# main.net
KiCad netlist of a schematic drawn in EAGLE
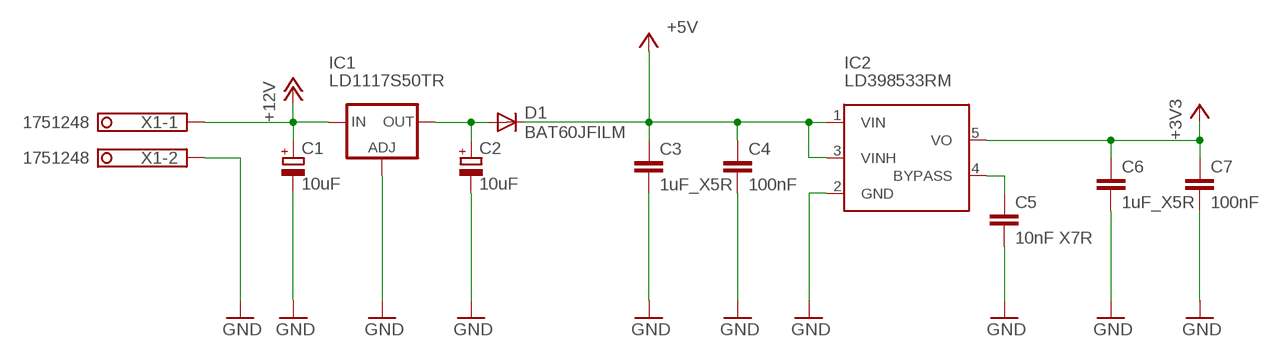
[diagram p0: schematic, sheet 1]
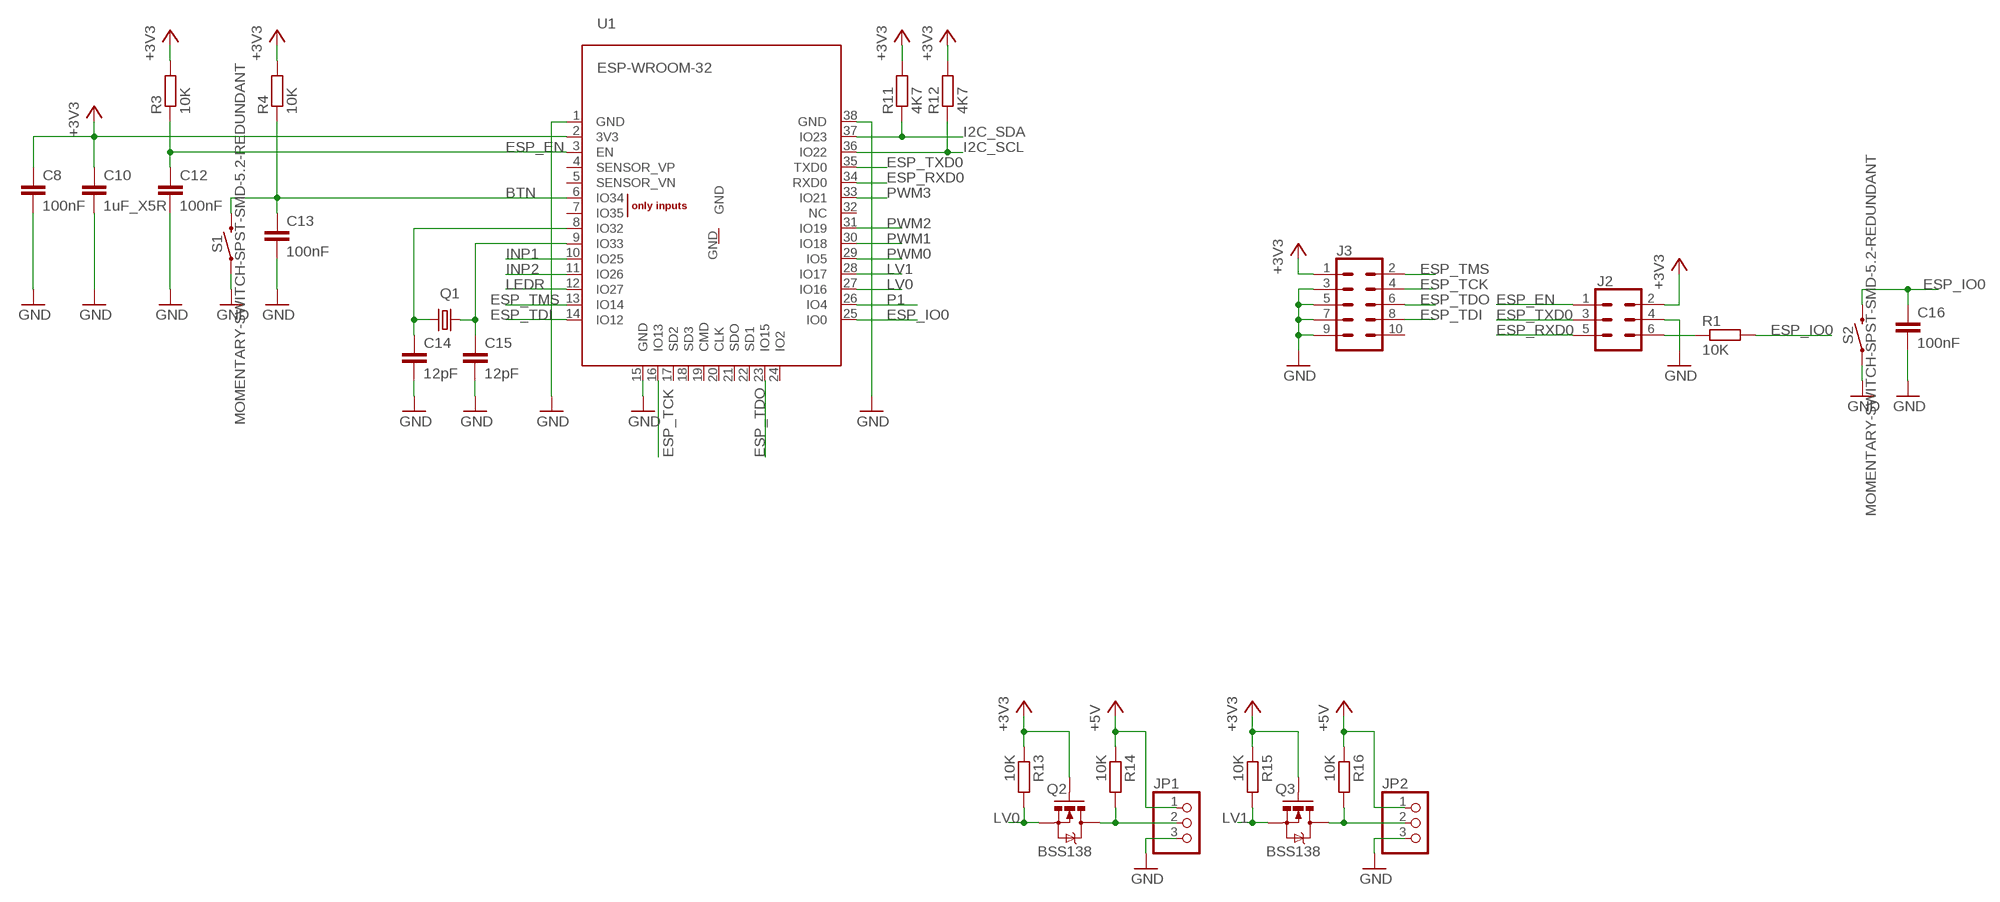
[diagram p1: schematic, sheet 2]
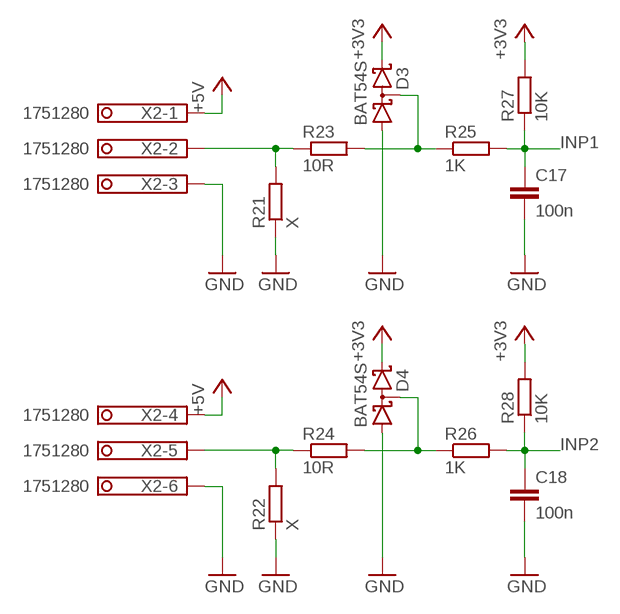
[diagram p2: schematic, sheet 3]
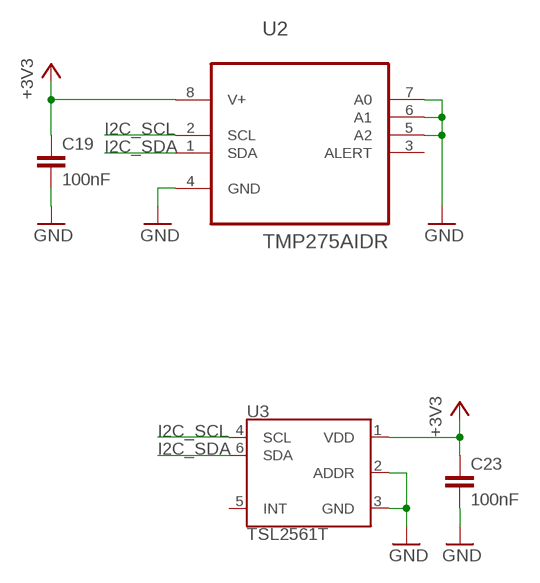
[diagram p3: schematic, sheet 4]
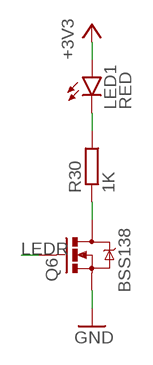
[diagram p4: schematic, sheet 5]
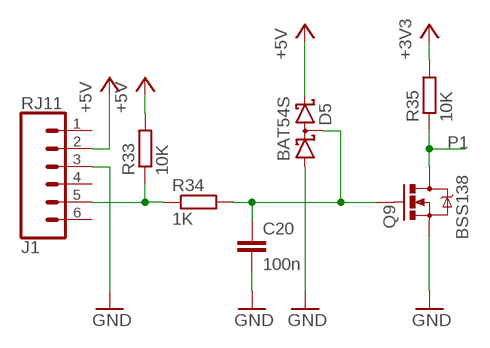
[diagram p5: schematic, sheet 6]
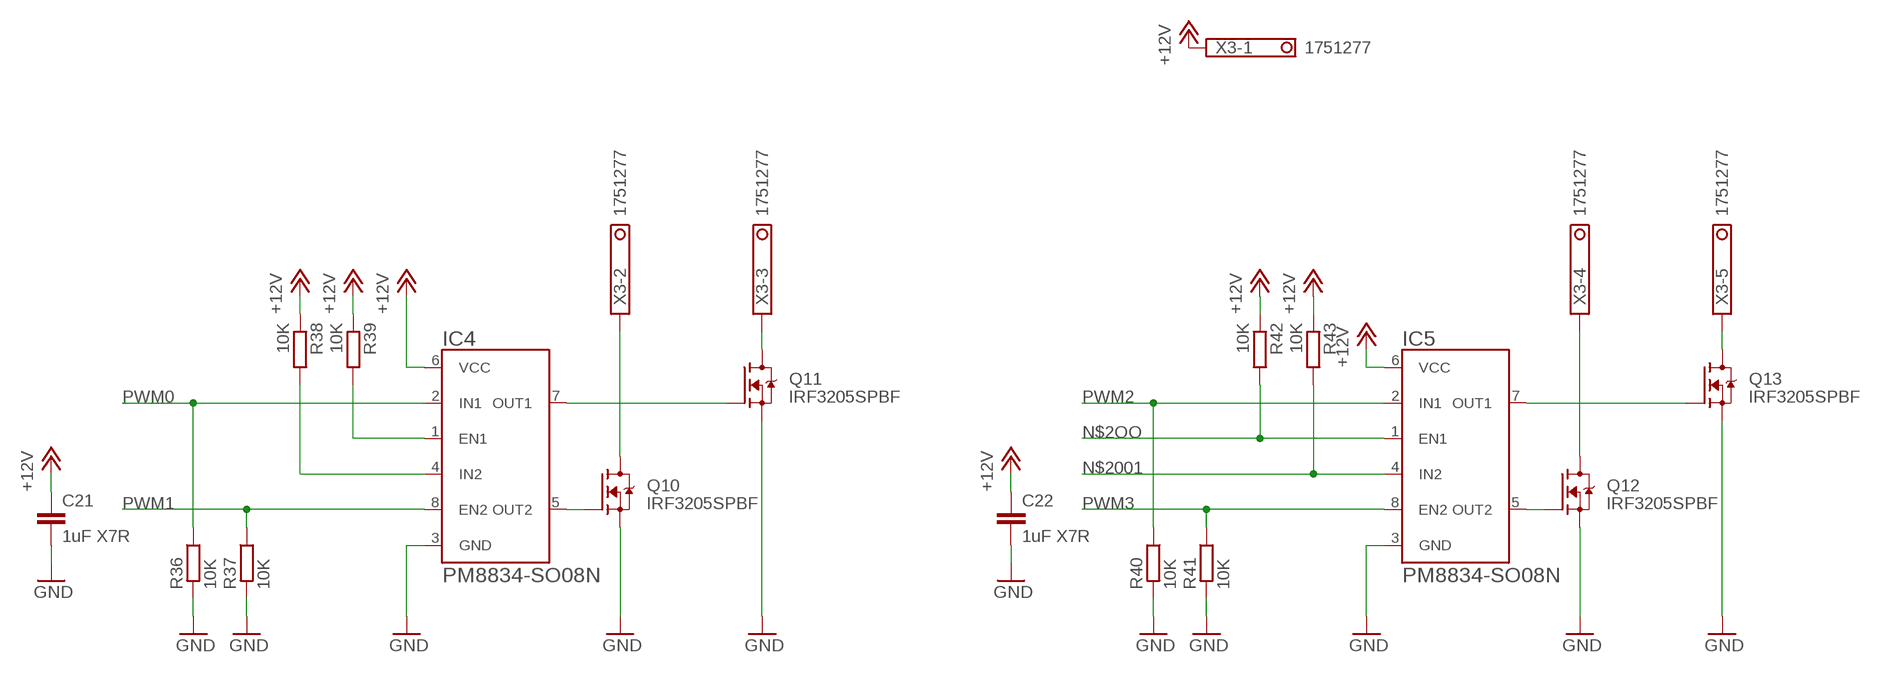
[diagram p6: schematic, sheet 7]
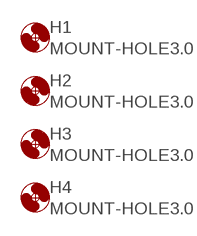
[diagram p7: schematic, sheet 8]

(export (version "E")
  (design (tool "Eeschema 10.0.6"))
  (components
    (comp (ref "C21")
      (value "1uF X7R")
      (footprint "eagle-import:C0805")
      (libsource (lib "eagle-import") (part "resistor_348_C-EUC0805"))
    )
    (comp (ref "C22")
      (value "1uF X7R")
      (footprint "eagle-import:C0805")
      (libsource (lib "eagle-import") (part "resistor_348_C-EUC0805"))
    )
    (comp (ref "IC4")
      (value "PM8834-SO08N")
      (footprint "eagle-import:SO08N")
      (fields (field (name "MF") "STMicroelectronics") (field (name "MP") "PM8834"))
      (libsource (lib "eagle-import") (part "PM8834-SO08N"))
    )
    (comp (ref "IC5")
      (value "PM8834-SO08N")
      (footprint "eagle-import:SO08N")
      (fields (field (name "MF") "STMicroelectronics") (field (name "MP") "PM8834"))
      (libsource (lib "eagle-import") (part "PM8834-SO08N"))
    )
    (comp (ref "Q10")
      (value "IRF3205SPBF")
      (footprint "eagle-import:TRANS_IRF3205SPBF")
      (fields (field (name "MF") "Infineon Technologies"))
      (libsource (lib "eagle-import") (part "IRF3205SPBF"))
    )
    (comp (ref "Q11")
      (value "IRF3205SPBF")
      (footprint "eagle-import:TRANS_IRF3205SPBF")
      (fields (field (name "MF") "Infineon Technologies"))
      (libsource (lib "eagle-import") (part "IRF3205SPBF"))
    )
    (comp (ref "Q12")
      (value "IRF3205SPBF")
      (footprint "eagle-import:TRANS_IRF3205SPBF")
      (fields (field (name "MF") "Infineon Technologies"))
      (libsource (lib "eagle-import") (part "IRF3205SPBF"))
    )
    (comp (ref "Q13")
      (value "IRF3205SPBF")
      (footprint "eagle-import:TRANS_IRF3205SPBF")
      (fields (field (name "MF") "Infineon Technologies"))
      (libsource (lib "eagle-import") (part "IRF3205SPBF"))
    )
    (comp (ref "R36")
      (value "10K")
      (footprint "eagle-import:R0805")
      (libsource (lib "eagle-import") (part "resistor_348_R-EU_R0805"))
    )
    (comp (ref "R37")
      (value "10K")
      (footprint "eagle-import:R0805")
      (libsource (lib "eagle-import") (part "resistor_348_R-EU_R0805"))
    )
    (comp (ref "R38")
      (value "10K")
      (footprint "eagle-import:R0805")
      (libsource (lib "eagle-import") (part "resistor_348_R-EU_R0805"))
    )
    (comp (ref "R39")
      (value "10K")
      (footprint "eagle-import:R0805")
      (libsource (lib "eagle-import") (part "resistor_348_R-EU_R0805"))
    )
    (comp (ref "R40")
      (value "10K")
      (footprint "eagle-import:R0805")
      (libsource (lib "eagle-import") (part "resistor_348_R-EU_R0805"))
    )
    (comp (ref "R41")
      (value "10K")
      (footprint "eagle-import:R0805")
      (libsource (lib "eagle-import") (part "resistor_348_R-EU_R0805"))
    )
    (comp (ref "R42")
      (value "10K")
      (footprint "eagle-import:R0805")
      (libsource (lib "eagle-import") (part "resistor_348_R-EU_R0805"))
    )
    (comp (ref "R43")
      (value "10K")
      (footprint "eagle-import:R0805")
      (libsource (lib "eagle-import") (part "resistor_348_R-EU_R0805"))
    )
    (comp (ref "X3")
      (value "1751277")
      (footprint "eagle-import:1751277")
      (libsource (lib "eagle-import") (part "1751277"))
    )
    (comp (ref "C19")
      (value "100nF")
      (footprint "eagle-import:C0805")
      (libsource (lib "eagle-import") (part "C-EUC0805"))
    )
    (comp (ref "C23")
      (value "100nF")
      (footprint "eagle-import:C0805")
      (libsource (lib "eagle-import") (part "C-EUC0805"))
    )
    (comp (ref "U2")
      (value "TMP275AIDR")
      (footprint "eagle-import:SOIC127P600X175-8N")
      (fields (field (name "MF") "Texas Instruments"))
      (libsource (lib "eagle-import") (part "TMP275AIDR"))
    )
    (comp (ref "U3")
      (value "TSL2561T")
      (footprint "eagle-import:TMB-6")
      (libsource (lib "eagle-import") (part "TSL2561T"))
    )
    (comp (ref "C20")
      (value "100n")
      (footprint "eagle-import:C0805")
      (libsource (lib "eagle-import") (part "resistor_348_C-EUC0805"))
    )
    (comp (ref "D5")
      (value "BAT54S")
      (footprint "eagle-import:SOT23")
      (libsource (lib "eagle-import") (part "BAT54S"))
    )
    (comp (ref "J1")
      (value "RJ11")
      (footprint "eagle-import:RJ11-6")
      (libsource (lib "eagle-import") (part "RJ11-6"))
    )
    (comp (ref "Q9")
      (value "BSS138")
      (footprint "eagle-import:SOT23-3")
      (libsource (lib "eagle-import") (part "MOSFET-NCHANNELSMD"))
    )
    (comp (ref "R33")
      (value "10K")
      (footprint "eagle-import:R0805")
      (libsource (lib "eagle-import") (part "resistor_348_R-EU_R0805"))
    )
    (comp (ref "R34")
      (value "1K")
      (footprint "eagle-import:R0805")
      (libsource (lib "eagle-import") (part "resistor_348_R-EU_R0805"))
    )
    (comp (ref "R35")
      (value "10K")
      (footprint "eagle-import:R0805")
      (libsource (lib "eagle-import") (part "resistor_348_R-EU_R0805"))
    )
    (comp (ref "C8")
      (value "100nF")
      (footprint "eagle-import:C0805")
      (libsource (lib "eagle-import") (part "resistor_348_C-EUC0805"))
    )
    (comp (ref "C10")
      (value "1uF_X5R")
      (footprint "eagle-import:C0805")
      (libsource (lib "eagle-import") (part "resistor_348_C-EUC0805"))
    )
    (comp (ref "C12")
      (value "100nF")
      (footprint "eagle-import:C0805")
      (libsource (lib "eagle-import") (part "resistor_348_C-EUC0805"))
    )
    (comp (ref "C13")
      (value "100nF")
      (footprint "eagle-import:C0805")
      (libsource (lib "eagle-import") (part "resistor_348_C-EUC0805"))
    )
    (comp (ref "C14")
      (value "12pF")
      (footprint "eagle-import:C0805")
      (libsource (lib "eagle-import") (part "resistor_348_C-EUC0805"))
    )
    (comp (ref "C15")
      (value "12pF")
      (footprint "eagle-import:C0805")
      (libsource (lib "eagle-import") (part "resistor_348_C-EUC0805"))
    )
    (comp (ref "C16")
      (value "100nF")
      (footprint "eagle-import:C0805")
      (libsource (lib "eagle-import") (part "resistor_348_C-EUC0805"))
    )
    (comp (ref "J2")
      (value "CONN_03X2SHROUD")
      (footprint "eagle-import:2X3-SHROUDED")
      (libsource (lib "eagle-import") (part "CONN_03X2SHROUD"))
    )
    (comp (ref "J3")
      (value "CONN_05X2SHD")
      (footprint "eagle-import:2X5-SHROUDED")
      (libsource (lib "eagle-import") (part "CONN_05X2SHD"))
    )
    (comp (ref "JP1")
      (value "PINHD-1X3")
      (footprint "eagle-import:1X03")
      (libsource (lib "eagle-import") (part "PINHD-1X3"))
    )
    (comp (ref "JP2")
      (value "PINHD-1X3")
      (footprint "eagle-import:1X03")
      (libsource (lib "eagle-import") (part "PINHD-1X3"))
    )
    (comp (ref "Q1")
      (value "CRYSTALTC38H")
      (footprint "eagle-import:TC38H")
      (libsource (lib "eagle-import") (part "CRYSTALTC38H"))
    )
    (comp (ref "Q2")
      (value "BSS138")
      (footprint "eagle-import:SOT23-3")
      (libsource (lib "eagle-import") (part "MOSFET-NCHANNELSMD"))
    )
    (comp (ref "Q3")
      (value "BSS138")
      (footprint "eagle-import:SOT23-3")
      (libsource (lib "eagle-import") (part "MOSFET-NCHANNELSMD"))
    )
    (comp (ref "R1")
      (value "10K")
      (footprint "eagle-import:R0805")
      (libsource (lib "eagle-import") (part "resistor_348_R-EU_R0805"))
    )
    (comp (ref "R3")
      (value "10K")
      (footprint "eagle-import:R0805")
      (libsource (lib "eagle-import") (part "R-EU_R0805"))
    )
    (comp (ref "R4")
      (value "10K")
      (footprint "eagle-import:R0805")
      (libsource (lib "eagle-import") (part "R-EU_R0805"))
    )
    (comp (ref "R11")
      (value "4K7")
      (footprint "eagle-import:R0805")
      (libsource (lib "eagle-import") (part "resistor_348_R-EU_R0805"))
    )
    (comp (ref "R12")
      (value "4K7")
      (footprint "eagle-import:R0805")
      (libsource (lib "eagle-import") (part "resistor_348_R-EU_R0805"))
    )
    (comp (ref "R13")
      (value "10K")
      (footprint "eagle-import:R0805")
      (libsource (lib "eagle-import") (part "resistor_348_R-EU_R0805"))
    )
    (comp (ref "R14")
      (value "10K")
      (footprint "eagle-import:R0805")
      (libsource (lib "eagle-import") (part "resistor_348_R-EU_R0805"))
    )
    (comp (ref "R15")
      (value "10K")
      (footprint "eagle-import:R0805")
      (libsource (lib "eagle-import") (part "resistor_348_R-EU_R0805"))
    )
    (comp (ref "R16")
      (value "10K")
      (footprint "eagle-import:R0805")
      (libsource (lib "eagle-import") (part "resistor_348_R-EU_R0805"))
    )
    (comp (ref "S1")
      (value "MOMENTARY-SWITCH-SPST-SMD-5.2-REDUNDANT")
      (footprint "eagle-import:TACTILE_SWITCH_SMD_5.2MM")
      (libsource (lib "eagle-import") (part "MOMENTARY-SWITCH-SPST-SMD-5.2-REDUNDANT"))
    )
    (comp (ref "S2")
      (value "MOMENTARY-SWITCH-SPST-SMD-5.2-REDUNDANT")
      (footprint "eagle-import:TACTILE_SWITCH_SMD_5.2MM")
      (libsource (lib "eagle-import") (part "MOMENTARY-SWITCH-SPST-SMD-5.2-REDUNDANT"))
    )
    (comp (ref "U1")
      (value "ESP-WROOM-32")
      (footprint "eagle-import:ESP-WROOM-32")
      (libsource (lib "eagle-import") (part "ESP-WROOM-32"))
    )
    (comp (ref "H1")
      (value "MOUNT-HOLE3.0")
      (footprint "eagle-import:3,0")
      (libsource (lib "eagle-import") (part "MOUNT-HOLE3.0"))
    )
    (comp (ref "H2")
      (value "MOUNT-HOLE3.0")
      (footprint "eagle-import:3,0")
      (libsource (lib "eagle-import") (part "MOUNT-HOLE3.0"))
    )
    (comp (ref "H3")
      (value "MOUNT-HOLE3.0")
      (footprint "eagle-import:3,0")
      (libsource (lib "eagle-import") (part "MOUNT-HOLE3.0"))
    )
    (comp (ref "H4")
      (value "MOUNT-HOLE3.0")
      (footprint "eagle-import:3,0")
      (libsource (lib "eagle-import") (part "MOUNT-HOLE3.0"))
    )
    (comp (ref "LED1")
      (value "RED")
      (footprint "eagle-import:CHIPLED_0805")
      (libsource (lib "eagle-import") (part "LEDCHIPLED_0805"))
    )
    (comp (ref "Q6")
      (value "BSS138")
      (footprint "eagle-import:SOT23-3")
      (libsource (lib "eagle-import") (part "MOSFET-NCHANNELSMD"))
    )
    (comp (ref "R30")
      (value "1K")
      (footprint "eagle-import:R0805")
      (libsource (lib "eagle-import") (part "resistor_348_R-EU_R0805"))
    )
    (comp (ref "C17")
      (value "100n")
      (footprint "eagle-import:C0805")
      (libsource (lib "eagle-import") (part "resistor_348_C-EUC0805"))
    )
    (comp (ref "C18")
      (value "100n")
      (footprint "eagle-import:C0805")
      (libsource (lib "eagle-import") (part "resistor_348_C-EUC0805"))
    )
    (comp (ref "D3")
      (value "BAT54S")
      (footprint "eagle-import:SOT23")
      (libsource (lib "eagle-import") (part "BAT54S"))
    )
    (comp (ref "D4")
      (value "BAT54S")
      (footprint "eagle-import:SOT23")
      (libsource (lib "eagle-import") (part "BAT54S"))
    )
    (comp (ref "R21")
      (value "X")
      (footprint "eagle-import:R0805")
      (libsource (lib "eagle-import") (part "resistor_348_R-EU_R0805"))
    )
    (comp (ref "R22")
      (value "X")
      (footprint "eagle-import:R0805")
      (libsource (lib "eagle-import") (part "resistor_348_R-EU_R0805"))
    )
    (comp (ref "R23")
      (value "10R")
      (footprint "eagle-import:R0805")
      (libsource (lib "eagle-import") (part "resistor_348_R-EU_R0805"))
    )
    (comp (ref "R24")
      (value "10R")
      (footprint "eagle-import:R0805")
      (libsource (lib "eagle-import") (part "resistor_348_R-EU_R0805"))
    )
    (comp (ref "R25")
      (value "1K")
      (footprint "eagle-import:R0805")
      (libsource (lib "eagle-import") (part "resistor_348_R-EU_R0805"))
    )
    (comp (ref "R26")
      (value "1K")
      (footprint "eagle-import:R0805")
      (libsource (lib "eagle-import") (part "resistor_348_R-EU_R0805"))
    )
    (comp (ref "R27")
      (value "10K")
      (footprint "eagle-import:R0805")
      (libsource (lib "eagle-import") (part "resistor_348_R-EU_R0805"))
    )
    (comp (ref "R28")
      (value "10K")
      (footprint "eagle-import:R0805")
      (libsource (lib "eagle-import") (part "resistor_348_R-EU_R0805"))
    )
    (comp (ref "X2")
      (value "1751280")
      (footprint "eagle-import:1751280")
      (libsource (lib "eagle-import") (part "1751280"))
    )
    (comp (ref "C1")
      (value "10uF")
      (footprint "eagle-import:SMC_C")
      (libsource (lib "eagle-import") (part "CPOL-EUSMCC"))
    )
    (comp (ref "C2")
      (value "10uF")
      (footprint "eagle-import:SMC_C")
      (libsource (lib "eagle-import") (part "CPOL-EUSMCC"))
    )
    (comp (ref "C3")
      (value "1uF_X5R")
      (footprint "eagle-import:C0805")
      (libsource (lib "eagle-import") (part "resistor_348_C-EUC0805"))
    )
    (comp (ref "C4")
      (value "100nF")
      (footprint "eagle-import:C0805")
      (libsource (lib "eagle-import") (part "resistor_348_C-EUC0805"))
    )
    (comp (ref "C5")
      (value "10nF X7R")
      (footprint "eagle-import:C0805")
      (libsource (lib "eagle-import") (part "resistor_348_C-EUC0805"))
    )
    (comp (ref "C6")
      (value "1uF_X5R")
      (footprint "eagle-import:C0805")
      (libsource (lib "eagle-import") (part "resistor_348_C-EUC0805"))
    )
    (comp (ref "C7")
      (value "100nF")
      (footprint "eagle-import:C0805")
      (libsource (lib "eagle-import") (part "resistor_348_C-EUC0805"))
    )
    (comp (ref "D1")
      (value "BAT60JFILM")
      (footprint "eagle-import:SOD323-W")
      (libsource (lib "eagle-import") (part "DIODE-SOD323-W"))
    )
    (comp (ref "IC1")
      (value "LD1117S50TR")
      (footprint "eagle-import:SOT223")
      (libsource (lib "eagle-import") (part "LD117A?S50TR"))
    )
    (comp (ref "IC2")
      (value "LD398533RM")
      (footprint "eagle-import:SOT23-5L")
      (libsource (lib "eagle-import") (part "LD3985M33R"))
    )
    (comp (ref "X1")
      (value "1751248")
      (footprint "eagle-import:1751248")
      (libsource (lib "eagle-import") (part "1751248"))
    )
  )
  (nets
    (net (code "1") (name "+3V3") (class "Default")
      (node (ref "C10") (pin "1") (pinfunction "1_1") (pintype "passive"))
      (node (ref "C19") (pin "1") (pinfunction "1_1") (pintype "passive"))
      (node (ref "C23") (pin "1") (pinfunction "1_1") (pintype "passive"))
      (node (ref "C6") (pin "1") (pinfunction "1_1") (pintype "passive"))
      (node (ref "C7") (pin "1") (pinfunction "1_1") (pintype "passive"))
      (node (ref "C8") (pin "1") (pinfunction "1_1") (pintype "passive"))
      (node (ref "D3") (pin "2") (pinfunction "C2_2") (pintype "passive"))
      (node (ref "D4") (pin "2") (pinfunction "C2_2") (pintype "passive"))
      (node (ref "IC2") (pin "5") (pinfunction "VO_5") (pintype "output"))
      (node (ref "J2") (pin "2") (pinfunction "2_2") (pintype "bidirectional"))
      (node (ref "J3") (pin "1") (pinfunction "1_1") (pintype "passive"))
      (node (ref "LED1") (pin "A") (pinfunction "A_A") (pintype "passive"))
      (node (ref "Q2") (pin "1") (pinfunction "G_1") (pintype "passive"))
      (node (ref "Q3") (pin "1") (pinfunction "G_1") (pintype "passive"))
      (node (ref "R11") (pin "2") (pinfunction "2_2") (pintype "passive"))
      (node (ref "R12") (pin "2") (pinfunction "2_2") (pintype "passive"))
      (node (ref "R13") (pin "1") (pinfunction "1_1") (pintype "passive"))
      (node (ref "R15") (pin "1") (pinfunction "1_1") (pintype "passive"))
      (node (ref "R27") (pin "2") (pinfunction "2_2") (pintype "passive"))
      (node (ref "R28") (pin "2") (pinfunction "2_2") (pintype "passive"))
      (node (ref "R3") (pin "2") (pinfunction "2_2") (pintype "passive"))
      (node (ref "R35") (pin "2") (pinfunction "2_2") (pintype "passive"))
      (node (ref "R4") (pin "2") (pinfunction "2_2") (pintype "passive"))
      (node (ref "U1") (pin "2") (pinfunction "3V3_2") (pintype "bidirectional"))
      (node (ref "U2") (pin "8") (pinfunction "V+_8") (pintype "power_in"))
      (node (ref "U3") (pin "1") (pinfunction "VDD_1") (pintype "power_in"))
    )
    (net (code "2") (name "+5V") (class "Default")
      (node (ref "C3") (pin "1") (pinfunction "1_1") (pintype "passive"))
      (node (ref "C4") (pin "1") (pinfunction "1_1") (pintype "passive"))
      (node (ref "D1") (pin "C") (pinfunction "C_C") (pintype "passive"))
      (node (ref "D5") (pin "2") (pinfunction "C2_2") (pintype "passive"))
      (node (ref "IC2") (pin "1") (pinfunction "VIN_1") (pintype "input"))
      (node (ref "IC2") (pin "3") (pinfunction "VINH_3") (pintype "input"))
      (node (ref "J1") (pin "2") (pinfunction "2_2") (pintype "passive"))
      (node (ref "JP1") (pin "1") (pinfunction "1_1") (pintype "passive"))
      (node (ref "JP2") (pin "1") (pinfunction "1_1") (pintype "passive"))
      (node (ref "R14") (pin "1") (pinfunction "1_1") (pintype "passive"))
      (node (ref "R16") (pin "1") (pinfunction "1_1") (pintype "passive"))
      (node (ref "R33") (pin "2") (pinfunction "2_2") (pintype "passive"))
      (node (ref "X2") (pin "1") (pinfunction "K_1") (pintype "passive"))
      (node (ref "X2") (pin "4") (pinfunction "K_4") (pintype "passive"))
    )
    (net (code "3") (name "+12V") (class "Default")
      (node (ref "C1") (pin "+") (pinfunction "+_+") (pintype "passive"))
      (node (ref "C21") (pin "1") (pinfunction "1_1") (pintype "passive"))
      (node (ref "C22") (pin "1") (pinfunction "1_1") (pintype "passive"))
      (node (ref "IC1") (pin "3") (pinfunction "IN_3") (pintype "input"))
      (node (ref "IC4") (pin "6") (pinfunction "VCC_6") (pintype "power_in"))
      (node (ref "IC5") (pin "6") (pinfunction "VCC_6") (pintype "power_in"))
      (node (ref "R38") (pin "2") (pinfunction "2_2") (pintype "passive"))
      (node (ref "R39") (pin "2") (pinfunction "2_2") (pintype "passive"))
      (node (ref "R42") (pin "2") (pinfunction "2_2") (pintype "passive"))
      (node (ref "R43") (pin "2") (pinfunction "2_2") (pintype "passive"))
      (node (ref "X1") (pin "1") (pinfunction "K_1") (pintype "passive"))
      (node (ref "X3") (pin "1") (pinfunction "K_1") (pintype "passive"))
    )
    (net (code "4") (name "BTN") (class "Default")
      (node (ref "C13") (pin "1") (pinfunction "1_1") (pintype "passive"))
      (node (ref "R4") (pin "1") (pinfunction "1_1") (pintype "passive"))
      (node (ref "S1") (pin "3") (pinfunction "2_3") (pintype "passive"))
      (node (ref "S1") (pin "4") (pinfunction "2_4") (pintype "passive"))
      (node (ref "U1") (pin "6") (pinfunction "IO34_6") (pintype "input"))
    )
    (net (code "5") (name "ESP_EN") (class "Default")
      (node (ref "C12") (pin "1") (pinfunction "1_1") (pintype "passive"))
      (node (ref "J2") (pin "1") (pinfunction "1_1") (pintype "bidirectional"))
      (node (ref "R3") (pin "1") (pinfunction "1_1") (pintype "passive"))
      (node (ref "U1") (pin "3") (pinfunction "EN_3") (pintype "bidirectional"))
    )
    (net (code "6") (name "ESP_IO0") (class "Default")
      (node (ref "C16") (pin "1") (pinfunction "1_1") (pintype "passive"))
      (node (ref "R1") (pin "2") (pinfunction "2_2") (pintype "passive"))
      (node (ref "S2") (pin "3") (pinfunction "2_3") (pintype "passive"))
      (node (ref "S2") (pin "4") (pinfunction "2_4") (pintype "passive"))
      (node (ref "U1") (pin "25") (pinfunction "IO0_25") (pintype "bidirectional"))
    )
    (net (code "7") (name "ESP_RXD0") (class "Default")
      (node (ref "J2") (pin "5") (pinfunction "5_5") (pintype "bidirectional"))
      (node (ref "U1") (pin "34") (pinfunction "RXD0_34") (pintype "bidirectional"))
    )
    (net (code "8") (name "ESP_TCK") (class "Default")
      (node (ref "J3") (pin "4") (pinfunction "4_4") (pintype "passive"))
      (node (ref "U1") (pin "16") (pinfunction "IO13_16") (pintype "bidirectional"))
    )
    (net (code "9") (name "ESP_TDI") (class "Default")
      (node (ref "J3") (pin "8") (pinfunction "8_8") (pintype "passive"))
      (node (ref "U1") (pin "14") (pinfunction "IO12_14") (pintype "bidirectional"))
    )
    (net (code "10") (name "ESP_TDO") (class "Default")
      (node (ref "J3") (pin "6") (pinfunction "6_6") (pintype "passive"))
      (node (ref "U1") (pin "23") (pinfunction "IO15_23") (pintype "bidirectional"))
    )
    (net (code "11") (name "ESP_TMS") (class "Default")
      (node (ref "J3") (pin "2") (pinfunction "2_2") (pintype "passive"))
      (node (ref "U1") (pin "13") (pinfunction "IO14_13") (pintype "bidirectional"))
    )
    (net (code "12") (name "ESP_TXD0") (class "Default")
      (node (ref "J2") (pin "3") (pinfunction "3_3") (pintype "bidirectional"))
      (node (ref "U1") (pin "35") (pinfunction "TXD0_35") (pintype "bidirectional"))
    )
    (net (code "13") (name "GND") (class "Default")
      (node (ref "C1") (pin "-") (pinfunction "-_-") (pintype "passive"))
      (node (ref "C10") (pin "2") (pinfunction "2_2") (pintype "passive"))
      (node (ref "C12") (pin "2") (pinfunction "2_2") (pintype "passive"))
      (node (ref "C13") (pin "2") (pinfunction "2_2") (pintype "passive"))
      (node (ref "C14") (pin "2") (pinfunction "2_2") (pintype "passive"))
      (node (ref "C15") (pin "2") (pinfunction "2_2") (pintype "passive"))
      (node (ref "C16") (pin "2") (pinfunction "2_2") (pintype "passive"))
      (node (ref "C17") (pin "2") (pinfunction "2_2") (pintype "passive"))
      (node (ref "C18") (pin "2") (pinfunction "2_2") (pintype "passive"))
      (node (ref "C19") (pin "2") (pinfunction "2_2") (pintype "passive"))
      (node (ref "C2") (pin "-") (pinfunction "-_-") (pintype "passive"))
      (node (ref "C20") (pin "2") (pinfunction "2_2") (pintype "passive"))
      (node (ref "C21") (pin "2") (pinfunction "2_2") (pintype "passive"))
      (node (ref "C22") (pin "2") (pinfunction "2_2") (pintype "passive"))
      (node (ref "C23") (pin "2") (pinfunction "2_2") (pintype "passive"))
      (node (ref "C3") (pin "2") (pinfunction "2_2") (pintype "passive"))
      (node (ref "C4") (pin "2") (pinfunction "2_2") (pintype "passive"))
      (node (ref "C5") (pin "2") (pinfunction "2_2") (pintype "passive"))
      (node (ref "C6") (pin "2") (pinfunction "2_2") (pintype "passive"))
      (node (ref "C7") (pin "2") (pinfunction "2_2") (pintype "passive"))
      (node (ref "C8") (pin "2") (pinfunction "2_2") (pintype "passive"))
      (node (ref "D3") (pin "1") (pinfunction "A1_1") (pintype "passive"))
      (node (ref "D4") (pin "1") (pinfunction "A1_1") (pintype "passive"))
      (node (ref "D5") (pin "1") (pinfunction "A1_1") (pintype "passive"))
      (node (ref "IC1") (pin "1") (pinfunction "ADJ_1") (pintype "input"))
      (node (ref "IC2") (pin "2") (pinfunction "GND_2") (pintype "power_in"))
      (node (ref "IC4") (pin "3") (pinfunction "GND_3") (pintype "power_in"))
      (node (ref "IC5") (pin "3") (pinfunction "GND_3") (pintype "power_in"))
      (node (ref "J1") (pin "3") (pinfunction "3_3") (pintype "passive"))
      (node (ref "J2") (pin "4") (pinfunction "4_4") (pintype "bidirectional"))
      (node (ref "J3") (pin "3") (pinfunction "3_3") (pintype "passive"))
      (node (ref "J3") (pin "5") (pinfunction "5_5") (pintype "passive"))
      (node (ref "J3") (pin "7") (pinfunction "7_7") (pintype "passive"))
      (node (ref "J3") (pin "9") (pinfunction "9_9") (pintype "passive"))
      (node (ref "JP1") (pin "3") (pinfunction "3_3") (pintype "passive"))
      (node (ref "JP2") (pin "3") (pinfunction "3_3") (pintype "passive"))
      (node (ref "Q10") (pin "3") (pinfunction "S_3") (pintype "passive"))
      (node (ref "Q11") (pin "3") (pinfunction "S_3") (pintype "passive"))
      (node (ref "Q12") (pin "3") (pinfunction "S_3") (pintype "passive"))
      (node (ref "Q13") (pin "3") (pinfunction "S_3") (pintype "passive"))
      (node (ref "Q6") (pin "2") (pinfunction "S_2") (pintype "passive"))
      (node (ref "Q9") (pin "2") (pinfunction "S_2") (pintype "passive"))
      (node (ref "R21") (pin "1") (pinfunction "1_1") (pintype "passive"))
      (node (ref "R22") (pin "1") (pinfunction "1_1") (pintype "passive"))
      (node (ref "R36") (pin "2") (pinfunction "2_2") (pintype "passive"))
      (node (ref "R37") (pin "2") (pinfunction "2_2") (pintype "passive"))
      (node (ref "R40") (pin "2") (pinfunction "2_2") (pintype "passive"))
      (node (ref "R41") (pin "2") (pinfunction "2_2") (pintype "passive"))
      (node (ref "S1") (pin "1") (pinfunction "1_1") (pintype "passive"))
      (node (ref "S1") (pin "2") (pinfunction "1_2") (pintype "passive"))
      (node (ref "S2") (pin "1") (pinfunction "1_1") (pintype "passive"))
      (node (ref "S2") (pin "2") (pinfunction "1_2") (pintype "passive"))
      (node (ref "U1") (pin "1") (pinfunction "GND_1") (pintype "bidirectional"))
      (node (ref "U1") (pin "15") (pinfunction "GND_15") (pintype "bidirectional"))
      (node (ref "U1") (pin "38") (pinfunction "GND_38") (pintype "bidirectional"))
      (node (ref "U2") (pin "4") (pinfunction "GND_4") (pintype "passive"))
      (node (ref "U2") (pin "5") (pinfunction "A2_5") (pintype "output"))
      (node (ref "U2") (pin "6") (pinfunction "A1_6") (pintype "output"))
      (node (ref "U2") (pin "7") (pinfunction "A0_7") (pintype "output"))
      (node (ref "U3") (pin "2") (pinfunction "ADDR_2") (pintype "input"))
      (node (ref "U3") (pin "3") (pinfunction "GND_3") (pintype "power_in"))
      (node (ref "X1") (pin "2") (pinfunction "K_2") (pintype "passive"))
      (node (ref "X2") (pin "3") (pinfunction "K_3") (pintype "passive"))
      (node (ref "X2") (pin "6") (pinfunction "K_6") (pintype "passive"))
    )
    (net (code "14") (name "I2C_SCL") (class "Default")
      (node (ref "R12") (pin "1") (pinfunction "1_1") (pintype "passive"))
      (node (ref "U1") (pin "36") (pinfunction "IO22_36") (pintype "bidirectional"))
      (node (ref "U2") (pin "2") (pinfunction "SCL_2") (pintype "input"))
      (node (ref "U3") (pin "4") (pinfunction "SCL_4") (pintype "input"))
    )
    (net (code "15") (name "I2C_SDA") (class "Default")
      (node (ref "R11") (pin "1") (pinfunction "1_1") (pintype "passive"))
      (node (ref "U1") (pin "37") (pinfunction "IO23_37") (pintype "bidirectional"))
      (node (ref "U2") (pin "1") (pinfunction "SDA_1") (pintype "input"))
      (node (ref "U3") (pin "6") (pinfunction "SDA_6") (pintype "bidirectional"))
    )
    (net (code "16") (name "INP1") (class "Default")
      (node (ref "C17") (pin "1") (pinfunction "1_1") (pintype "passive"))
      (node (ref "R25") (pin "2") (pinfunction "2_2") (pintype "passive"))
      (node (ref "R27") (pin "1") (pinfunction "1_1") (pintype "passive"))
      (node (ref "U1") (pin "10") (pinfunction "IO25_10") (pintype "bidirectional"))
    )
    (net (code "17") (name "INP2") (class "Default")
      (node (ref "C18") (pin "1") (pinfunction "1_1") (pintype "passive"))
      (node (ref "R26") (pin "2") (pinfunction "2_2") (pintype "passive"))
      (node (ref "R28") (pin "1") (pinfunction "1_1") (pintype "passive"))
      (node (ref "U1") (pin "11") (pinfunction "IO26_11") (pintype "bidirectional"))
    )
    (net (code "18") (name "LEDR") (class "Default")
      (node (ref "Q6") (pin "1") (pinfunction "G_1") (pintype "passive"))
      (node (ref "U1") (pin "12") (pinfunction "IO27_12") (pintype "bidirectional"))
    )
    (net (code "19") (name "LV0") (class "Default")
      (node (ref "Q2") (pin "2") (pinfunction "S_2") (pintype "passive"))
      (node (ref "R13") (pin "2") (pinfunction "2_2") (pintype "passive"))
      (node (ref "U1") (pin "27") (pinfunction "IO16_27") (pintype "bidirectional"))
    )
    (net (code "20") (name "LV1") (class "Default")
      (node (ref "Q3") (pin "2") (pinfunction "S_2") (pintype "passive"))
      (node (ref "R15") (pin "2") (pinfunction "2_2") (pintype "passive"))
      (node (ref "U1") (pin "28") (pinfunction "IO17_28") (pintype "bidirectional"))
    )
    (net (code "21") (name "N$2OO") (class "Default")
      (node (ref "IC5") (pin "1") (pinfunction "EN1_1") (pintype "input"))
      (node (ref "R42") (pin "1") (pinfunction "1_1") (pintype "passive"))
    )
    (net (code "22") (name "N$2001") (class "Default")
      (node (ref "IC5") (pin "4") (pinfunction "IN2_4") (pintype "input"))
      (node (ref "R43") (pin "1") (pinfunction "1_1") (pintype "passive"))
    )
    (net (code "23") (name "Net-(D3-C1A2)") (class "Default")
      (node (ref "D3") (pin "3") (pinfunction "C1A2_3") (pintype "passive"))
      (node (ref "R23") (pin "2") (pinfunction "2_2") (pintype "passive"))
      (node (ref "R25") (pin "1") (pinfunction "1_1") (pintype "passive"))
    )
    (net (code "24") (name "Net-(D4-C1A2)") (class "Default")
      (node (ref "D4") (pin "3") (pinfunction "C1A2_3") (pintype "passive"))
      (node (ref "R24") (pin "2") (pinfunction "2_2") (pintype "passive"))
      (node (ref "R26") (pin "1") (pinfunction "1_1") (pintype "passive"))
    )
    (net (code "25") (name "Net-(D5-C1A2)") (class "Default")
      (node (ref "C20") (pin "1") (pinfunction "1_1") (pintype "passive"))
      (node (ref "D5") (pin "3") (pinfunction "C1A2_3") (pintype "passive"))
      (node (ref "Q9") (pin "1") (pinfunction "G_1") (pintype "passive"))
      (node (ref "R34") (pin "2") (pinfunction "2_2") (pintype "passive"))
    )
    (net (code "26") (name "Net-(IC1-OUT)") (class "Default")
      (node (ref "C2") (pin "+") (pinfunction "+_+") (pintype "passive"))
      (node (ref "D1") (pin "A") (pinfunction "A_A") (pintype "passive"))
      (node (ref "IC1") (pin "4") (pinfunction "OUT_4") (pintype "passive"))
    )
    (net (code "27") (name "Net-(IC2-BYPASS)") (class "Default")
      (node (ref "C5") (pin "1") (pinfunction "1_1") (pintype "passive"))
      (node (ref "IC2") (pin "4") (pinfunction "BYPASS_4") (pintype "passive"))
    )
    (net (code "28") (name "Net-(IC4-EN1)") (class "Default")
      (node (ref "IC4") (pin "1") (pinfunction "EN1_1") (pintype "input"))
      (node (ref "R39") (pin "1") (pinfunction "1_1") (pintype "passive"))
    )
    (net (code "29") (name "Net-(IC4-IN2)") (class "Default")
      (node (ref "IC4") (pin "4") (pinfunction "IN2_4") (pintype "input"))
      (node (ref "R38") (pin "1") (pinfunction "1_1") (pintype "passive"))
    )
    (net (code "30") (name "Net-(IC4-OUT1)") (class "Default")
      (node (ref "IC4") (pin "7") (pinfunction "OUT1_7") (pintype "bidirectional"))
      (node (ref "Q11") (pin "1") (pinfunction "G_1") (pintype "passive"))
    )
    (net (code "31") (name "Net-(IC4-OUT2)") (class "Default")
      (node (ref "IC4") (pin "5") (pinfunction "OUT2_5") (pintype "bidirectional"))
      (node (ref "Q10") (pin "1") (pinfunction "G_1") (pintype "passive"))
    )
    (net (code "32") (name "Net-(IC5-OUT1)") (class "Default")
      (node (ref "IC5") (pin "7") (pinfunction "OUT1_7") (pintype "bidirectional"))
      (node (ref "Q13") (pin "1") (pinfunction "G_1") (pintype "passive"))
    )
    (net (code "33") (name "Net-(IC5-OUT2)") (class "Default")
      (node (ref "IC5") (pin "5") (pinfunction "OUT2_5") (pintype "bidirectional"))
      (node (ref "Q12") (pin "1") (pinfunction "G_1") (pintype "passive"))
    )
    (net (code "34") (name "Net-(J1-Pad5)") (class "Default")
      (node (ref "J1") (pin "5") (pinfunction "5_5") (pintype "passive"))
      (node (ref "R33") (pin "1") (pinfunction "1_1") (pintype "passive"))
      (node (ref "R34") (pin "1") (pinfunction "1_1") (pintype "passive"))
    )
    (net (code "35") (name "Net-(J2-Pad6)") (class "Default")
      (node (ref "J2") (pin "6") (pinfunction "6_6") (pintype "bidirectional"))
      (node (ref "R1") (pin "1") (pinfunction "1_1") (pintype "passive"))
    )
    (net (code "36") (name "Net-(LED1-PadC)") (class "Default")
      (node (ref "LED1") (pin "C") (pinfunction "C_C") (pintype "passive"))
      (node (ref "R30") (pin "1") (pinfunction "1_1") (pintype "passive"))
    )
    (net (code "37") (name "Net-(Q2-D)") (class "Default")
      (node (ref "JP1") (pin "2") (pinfunction "2_2") (pintype "passive"))
      (node (ref "Q2") (pin "3") (pinfunction "D_3") (pintype "passive"))
      (node (ref "R14") (pin "2") (pinfunction "2_2") (pintype "passive"))
    )
    (net (code "38") (name "Net-(Q3-D)") (class "Default")
      (node (ref "JP2") (pin "2") (pinfunction "2_2") (pintype "passive"))
      (node (ref "Q3") (pin "3") (pinfunction "D_3") (pintype "passive"))
      (node (ref "R16") (pin "2") (pinfunction "2_2") (pintype "passive"))
    )
    (net (code "39") (name "Net-(Q6-D)") (class "Default")
      (node (ref "Q6") (pin "3") (pinfunction "D_3") (pintype "passive"))
      (node (ref "R30") (pin "2") (pinfunction "2_2") (pintype "passive"))
    )
    (net (code "40") (name "Net-(Q10-D)") (class "Default")
      (node (ref "Q10") (pin "2") (pinfunction "D_2") (pintype "passive"))
      (node (ref "X3") (pin "2") (pinfunction "K_2") (pintype "passive"))
    )
    (net (code "41") (name "Net-(Q11-D)") (class "Default")
      (node (ref "Q11") (pin "2") (pinfunction "D_2") (pintype "passive"))
      (node (ref "X3") (pin "3") (pinfunction "K_3") (pintype "passive"))
    )
    (net (code "42") (name "Net-(Q12-D)") (class "Default")
      (node (ref "Q12") (pin "2") (pinfunction "D_2") (pintype "passive"))
      (node (ref "X3") (pin "4") (pinfunction "K_4") (pintype "passive"))
    )
    (net (code "43") (name "Net-(Q13-D)") (class "Default")
      (node (ref "Q13") (pin "2") (pinfunction "D_2") (pintype "passive"))
      (node (ref "X3") (pin "5") (pinfunction "K_5") (pintype "passive"))
    )
    (net (code "44") (name "Net-(U1-IO32)") (class "Default")
      (node (ref "C14") (pin "1") (pinfunction "1_1") (pintype "passive"))
      (node (ref "Q1") (pin "2") (pinfunction "2_2") (pintype "passive"))
      (node (ref "U1") (pin "8") (pinfunction "IO32_8") (pintype "bidirectional"))
    )
    (net (code "45") (name "Net-(U1-IO33)") (class "Default")
      (node (ref "C15") (pin "1") (pinfunction "1_1") (pintype "passive"))
      (node (ref "Q1") (pin "1") (pinfunction "1_1") (pintype "passive"))
      (node (ref "U1") (pin "9") (pinfunction "IO33_9") (pintype "bidirectional"))
    )
    (net (code "46") (name "Net-(X2B-K)") (class "Default")
      (node (ref "R21") (pin "2") (pinfunction "2_2") (pintype "passive"))
      (node (ref "R23") (pin "1") (pinfunction "1_1") (pintype "passive"))
      (node (ref "X2") (pin "2") (pinfunction "K_2") (pintype "passive"))
    )
    (net (code "47") (name "Net-(X2E-K)") (class "Default")
      (node (ref "R22") (pin "2") (pinfunction "2_2") (pintype "passive"))
      (node (ref "R24") (pin "1") (pinfunction "1_1") (pintype "passive"))
      (node (ref "X2") (pin "5") (pinfunction "K_5") (pintype "passive"))
    )
    (net (code "48") (name "P1") (class "Default")
      (node (ref "Q9") (pin "3") (pinfunction "D_3") (pintype "passive"))
      (node (ref "R35") (pin "1") (pinfunction "1_1") (pintype "passive"))
      (node (ref "U1") (pin "26") (pinfunction "IO4_26") (pintype "bidirectional"))
    )
    (net (code "49") (name "PWM0") (class "Default")
      (node (ref "IC4") (pin "2") (pinfunction "IN1_2") (pintype "input"))
      (node (ref "R36") (pin "1") (pinfunction "1_1") (pintype "passive"))
      (node (ref "U1") (pin "29") (pinfunction "IO5_29") (pintype "bidirectional"))
    )
    (net (code "50") (name "PWM1") (class "Default")
      (node (ref "IC4") (pin "8") (pinfunction "EN2_8") (pintype "input"))
      (node (ref "R37") (pin "1") (pinfunction "1_1") (pintype "passive"))
      (node (ref "U1") (pin "30") (pinfunction "IO18_30") (pintype "bidirectional"))
    )
    (net (code "51") (name "PWM2") (class "Default")
      (node (ref "IC5") (pin "2") (pinfunction "IN1_2") (pintype "input"))
      (node (ref "R40") (pin "1") (pinfunction "1_1") (pintype "passive"))
      (node (ref "U1") (pin "31") (pinfunction "IO19_31") (pintype "bidirectional"))
    )
    (net (code "52") (name "PWM3") (class "Default")
      (node (ref "IC5") (pin "8") (pinfunction "EN2_8") (pintype "input"))
      (node (ref "R41") (pin "1") (pinfunction "1_1") (pintype "passive"))
      (node (ref "U1") (pin "33") (pinfunction "IO21_33") (pintype "bidirectional"))
    )
    (net (code "53") (name "unconnected-(J1-Pad1)") (class "Default")
      (node (ref "J1") (pin "1") (pinfunction "1_1") (pintype "passive"))
    )
    (net (code "54") (name "unconnected-(J1-Pad4)") (class "Default")
      (node (ref "J1") (pin "4") (pinfunction "4_4") (pintype "passive"))
    )
    (net (code "55") (name "unconnected-(J1-Pad6)") (class "Default")
      (node (ref "J1") (pin "6") (pinfunction "6_6") (pintype "passive"))
    )
    (net (code "56") (name "unconnected-(J3-Pad10)") (class "Default")
      (node (ref "J3") (pin "10") (pinfunction "10_10") (pintype "passive"))
    )
    (net (code "57") (name "unconnected-(U1-CLK-Pad20)") (class "Default")
      (node (ref "U1") (pin "20") (pinfunction "CLK_20") (pintype "bidirectional"))
    )
    (net (code "58") (name "unconnected-(U1-CMD-Pad19)") (class "Default")
      (node (ref "U1") (pin "19") (pinfunction "CMD_19") (pintype "bidirectional"))
    )
    (net (code "59") (name "unconnected-(U1-IO2-Pad24)") (class "Default")
      (node (ref "U1") (pin "24") (pinfunction "IO2_24") (pintype "bidirectional"))
    )
    (net (code "60") (name "unconnected-(U1-IO35-Pad7)") (class "Default")
      (node (ref "U1") (pin "7") (pinfunction "IO35_7") (pintype "input"))
    )
    (net (code "61") (name "unconnected-(U1-NC-Pad32)") (class "Default")
      (node (ref "U1") (pin "32") (pinfunction "NC_32") (pintype "bidirectional"))
    )
    (net (code "62") (name "unconnected-(U1-PadGND)") (class "Default")
      (node (ref "U1") (pin "GND") (pinfunction "GND_GND") (pintype "bidirectional"))
    )
    (net (code "63") (name "unconnected-(U1-SD1-Pad22)") (class "Default")
      (node (ref "U1") (pin "22") (pinfunction "SD1_22") (pintype "bidirectional"))
    )
    (net (code "64") (name "unconnected-(U1-SD2-Pad17)") (class "Default")
      (node (ref "U1") (pin "17") (pinfunction "SD2_17") (pintype "bidirectional"))
    )
    (net (code "65") (name "unconnected-(U1-SD3-Pad18)") (class "Default")
      (node (ref "U1") (pin "18") (pinfunction "SD3_18") (pintype "bidirectional"))
    )
    (net (code "66") (name "unconnected-(U1-SDO-Pad21)") (class "Default")
      (node (ref "U1") (pin "21") (pinfunction "SDO_21") (pintype "bidirectional"))
    )
    (net (code "67") (name "unconnected-(U1-SENSOR_VN-Pad5)") (class "Default")
      (node (ref "U1") (pin "5") (pinfunction "SENSOR_VN_5") (pintype "input"))
    )
    (net (code "68") (name "unconnected-(U1-SENSOR_VP-Pad4)") (class "Default")
      (node (ref "U1") (pin "4") (pinfunction "SENSOR_VP_4") (pintype "input"))
    )
    (net (code "69") (name "unconnected-(U2-ALERT-Pad3)") (class "Default")
      (node (ref "U2") (pin "3") (pinfunction "ALERT_3") (pintype "output"))
    )
    (net (code "70") (name "unconnected-(U3-INT-Pad5)") (class "Default")
      (node (ref "U3") (pin "5") (pinfunction "INT_5") (pintype "output"))
    )
  )
)
